# SMARTCONTROL.net
KiCad netlist of a schematic drawn in EAGLE
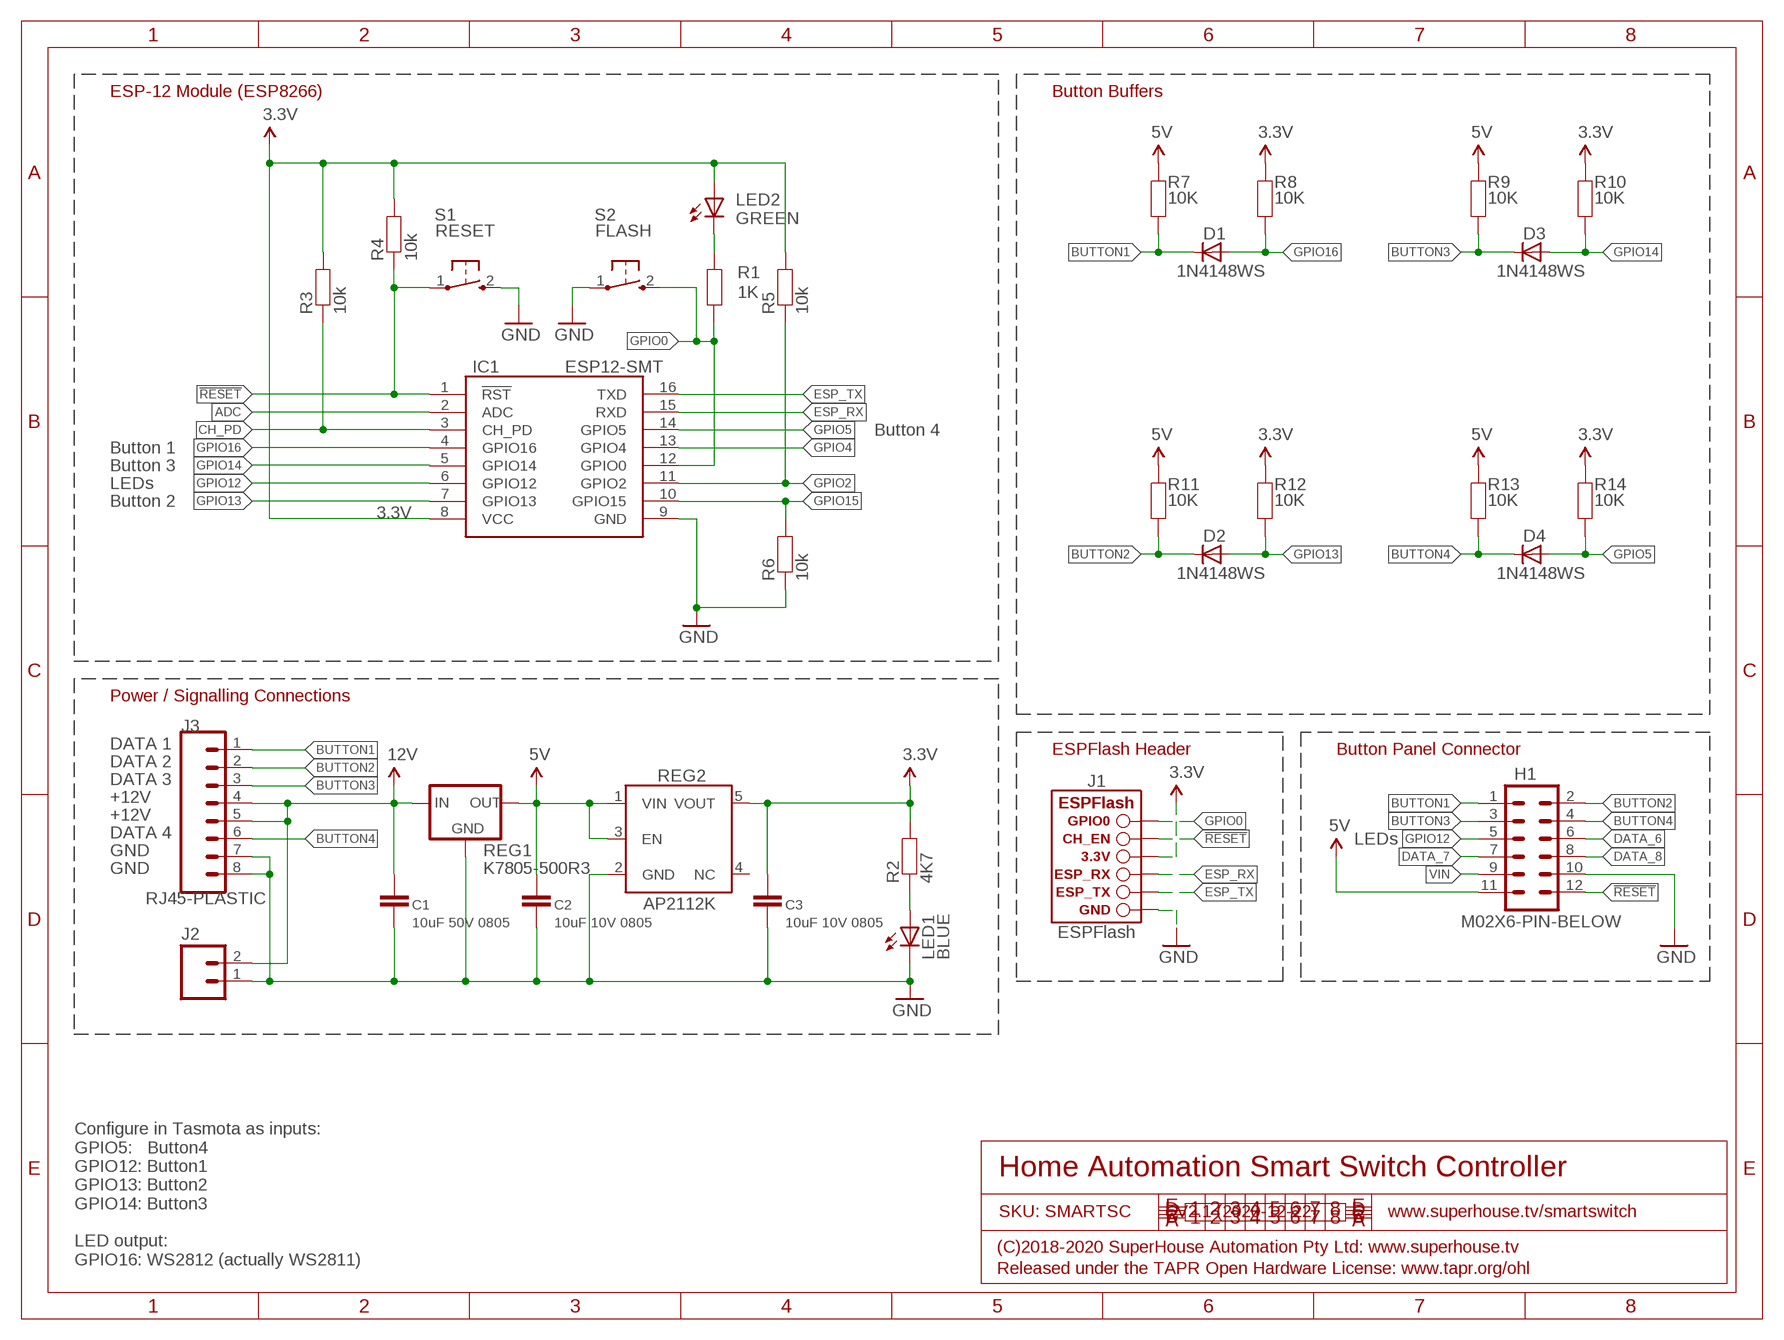
[diagram p0: schematic, sheet 1]

(export (version "E")
  (design (tool "Eeschema 10.0.6"))
  (components
    (comp (ref "C1")
      (value "10uF 50V 0805")
      (footprint "eagle-import:C0805")
      (libsource (lib "eagle-import") (part "CAP0805"))
    )
    (comp (ref "C2")
      (value "10uF 10V 0805")
      (footprint "eagle-import:C0805")
      (libsource (lib "eagle-import") (part "CAP0805"))
    )
    (comp (ref "C3")
      (value "10uF 10V 0805")
      (footprint "eagle-import:C0805")
      (libsource (lib "eagle-import") (part "CAP0805"))
    )
    (comp (ref "D1")
      (value "1N4148WS")
      (footprint "eagle-import:SOD-323")
      (libsource (lib "eagle-import") (part "DIODESOD"))
    )
    (comp (ref "D2")
      (value "1N4148WS")
      (footprint "eagle-import:SOD-323")
      (libsource (lib "eagle-import") (part "DIODESOD"))
    )
    (comp (ref "D3")
      (value "1N4148WS")
      (footprint "eagle-import:SOD-323")
      (libsource (lib "eagle-import") (part "DIODESOD"))
    )
    (comp (ref "D4")
      (value "1N4148WS")
      (footprint "eagle-import:SOD-323")
      (libsource (lib "eagle-import") (part "DIODESOD"))
    )
    (comp (ref "H1")
      (value "M02X6-PIN-BELOW")
      (footprint "eagle-import:2X06-P-BELOW")
      (libsource (lib "eagle-import") (part "M02X6-PIN-BELOW"))
    )
    (comp (ref "IC1")
      (value "ESP12-SMT")
      (footprint "eagle-import:ESP12")
      (libsource (lib "eagle-import") (part "ESP12-SMT"))
    )
    (comp (ref "J1")
      (value "ESPFLASH-1X6-2.54-SOCKET")
      (footprint "eagle-import:1X6-2.54-SOCKET")
      (libsource (lib "eagle-import") (part "ESPFLASH-1X6-2.54-SOCKET"))
    )
    (comp (ref "J2")
      (value "M02-SCREW-5MM")
      (footprint "eagle-import:SCREWTERMINAL-5MM-2")
      (libsource (lib "eagle-import") (part "M02-SCREW-5MM"))
    )
    (comp (ref "J3")
      (value "RJ45-PLASTIC")
      (footprint "eagle-import:RJ45")
      (libsource (lib "eagle-import") (part "RJ45-PLASTIC"))
    )
    (comp (ref "LED1")
      (value "BLUE")
      (footprint "eagle-import:LED-0603")
      (libsource (lib "eagle-import") (part "LED0603"))
    )
    (comp (ref "LED2")
      (value "GREEN")
      (footprint "eagle-import:LED-0603")
      (libsource (lib "eagle-import") (part "LED0603"))
    )
    (comp (ref "R1")
      (value "1K")
      (footprint "eagle-import:R0603")
      (libsource (lib "eagle-import") (part "RESISTOR0603"))
    )
    (comp (ref "R2")
      (value "4K7")
      (footprint "eagle-import:R0603")
      (libsource (lib "eagle-import") (part "RESISTOR0603"))
    )
    (comp (ref "R3")
      (value "10k")
      (footprint "eagle-import:R0603")
      (libsource (lib "eagle-import") (part "RESISTOR0603"))
    )
    (comp (ref "R4")
      (value "10k")
      (footprint "eagle-import:R0603")
      (libsource (lib "eagle-import") (part "RESISTOR0603"))
    )
    (comp (ref "R5")
      (value "10k")
      (footprint "eagle-import:R0603")
      (libsource (lib "eagle-import") (part "RESISTOR0603"))
    )
    (comp (ref "R6")
      (value "10k")
      (footprint "eagle-import:R0603")
      (libsource (lib "eagle-import") (part "RESISTOR0603"))
    )
    (comp (ref "R7")
      (value "10K")
      (footprint "eagle-import:R0603")
      (libsource (lib "eagle-import") (part "RESISTOR0603"))
    )
    (comp (ref "R8")
      (value "10K")
      (footprint "eagle-import:R0603")
      (libsource (lib "eagle-import") (part "RESISTOR0603"))
    )
    (comp (ref "R9")
      (value "10K")
      (footprint "eagle-import:R0603")
      (libsource (lib "eagle-import") (part "RESISTOR0603"))
    )
    (comp (ref "R10")
      (value "10K")
      (footprint "eagle-import:R0603")
      (libsource (lib "eagle-import") (part "RESISTOR0603"))
    )
    (comp (ref "R11")
      (value "10K")
      (footprint "eagle-import:R0603")
      (libsource (lib "eagle-import") (part "RESISTOR0603"))
    )
    (comp (ref "R12")
      (value "10K")
      (footprint "eagle-import:R0603")
      (libsource (lib "eagle-import") (part "RESISTOR0603"))
    )
    (comp (ref "R13")
      (value "10K")
      (footprint "eagle-import:R0603")
      (libsource (lib "eagle-import") (part "RESISTOR0603"))
    )
    (comp (ref "R14")
      (value "10K")
      (footprint "eagle-import:R0603")
      (libsource (lib "eagle-import") (part "RESISTOR0603"))
    )
    (comp (ref "REG1")
      (value "K7805-500R3")
      (footprint "eagle-import:K78XX-500R3")
      (libsource (lib "eagle-import") (part "78XX-K78XX-VERTICAL"))
    )
    (comp (ref "REG2")
      (value "AP2112KSOT25")
      (footprint "eagle-import:SOT23-5")
      (libsource (lib "eagle-import") (part "AP2112KSOT25"))
    )
    (comp (ref "S1")
      (value "RESET")
      (footprint "eagle-import:TACTILE_SMT_3X4X2")
      (libsource (lib "eagle-import") (part "TAC_SWITCH_2PINSMT"))
    )
    (comp (ref "S2")
      (value "FLASH")
      (footprint "eagle-import:TACTILE_SMT_3X4X2")
      (libsource (lib "eagle-import") (part "TAC_SWITCH_2PINSMT"))
    )
  )
  (nets
    (net (code "1") (name "/~{RESET}") (class "Default")
      (node (ref "H1") (pin "12") (pinfunction "12_12") (pintype "passive"))
      (node (ref "IC1") (pin "1") (pinfunction "~{RST}_1") (pintype "bidirectional"))
      (node (ref "J1") (pin "5") (pinfunction "CH_EN_5") (pintype "passive"))
      (node (ref "R4") (pin "1") (pinfunction "1_1") (pintype "passive"))
      (node (ref "S1") (pin "1") (pinfunction "P_1") (pintype "passive"))
    )
    (net (code "2") (name "3.3V") (class "Default")
      (node (ref "C3") (pin "1") (pinfunction "1_1") (pintype "passive"))
      (node (ref "IC1") (pin "8") (pinfunction "VCC_8") (pintype "power_in"))
      (node (ref "J1") (pin "4") (pinfunction "3.3V_4") (pintype "passive"))
      (node (ref "LED2") (pin "A") (pinfunction "A_A") (pintype "passive"))
      (node (ref "R10") (pin "2") (pinfunction "2_2") (pintype "passive"))
      (node (ref "R12") (pin "2") (pinfunction "2_2") (pintype "passive"))
      (node (ref "R14") (pin "2") (pinfunction "2_2") (pintype "passive"))
      (node (ref "R2") (pin "2") (pinfunction "2_2") (pintype "passive"))
      (node (ref "R3") (pin "2") (pinfunction "2_2") (pintype "passive"))
      (node (ref "R4") (pin "2") (pinfunction "2_2") (pintype "passive"))
      (node (ref "R5") (pin "2") (pinfunction "2_2") (pintype "passive"))
      (node (ref "R8") (pin "2") (pinfunction "2_2") (pintype "passive"))
      (node (ref "REG2") (pin "5") (pinfunction "VOUT_5") (pintype "bidirectional"))
    )
    (net (code "3") (name "5V") (class "Default")
      (node (ref "C2") (pin "1") (pinfunction "1_1") (pintype "passive"))
      (node (ref "H1") (pin "11") (pinfunction "11_11") (pintype "passive"))
      (node (ref "R11") (pin "2") (pinfunction "2_2") (pintype "passive"))
      (node (ref "R13") (pin "2") (pinfunction "2_2") (pintype "passive"))
      (node (ref "R7") (pin "2") (pinfunction "2_2") (pintype "passive"))
      (node (ref "R9") (pin "2") (pinfunction "2_2") (pintype "passive"))
      (node (ref "REG1") (pin "3") (pinfunction "OUT_3") (pintype "output"))
      (node (ref "REG2") (pin "1") (pinfunction "VIN_1") (pintype "bidirectional"))
      (node (ref "REG2") (pin "3") (pinfunction "EN_3") (pintype "bidirectional"))
    )
    (net (code "4") (name "12V") (class "Default")
      (node (ref "C1") (pin "1") (pinfunction "1_1") (pintype "passive"))
      (node (ref "J2") (pin "2") (pinfunction "2_2") (pintype "passive"))
      (node (ref "J3") (pin "4") (pinfunction "4_4") (pintype "passive"))
      (node (ref "J3") (pin "5") (pinfunction "5_5") (pintype "passive"))
      (node (ref "REG1") (pin "1") (pinfunction "IN_1") (pintype "input"))
    )
    (net (code "5") (name "ADC") (class "Default")
      (node (ref "IC1") (pin "2") (pinfunction "ADC_2") (pintype "input"))
    )
    (net (code "6") (name "BUTTON1") (class "Default")
      (node (ref "D1") (pin "1") (pinfunction "C_1") (pintype "passive"))
      (node (ref "H1") (pin "1") (pinfunction "1_1") (pintype "passive"))
      (node (ref "J3") (pin "1") (pinfunction "1_1") (pintype "passive"))
      (node (ref "R7") (pin "1") (pinfunction "1_1") (pintype "passive"))
    )
    (net (code "7") (name "BUTTON2") (class "Default")
      (node (ref "D2") (pin "1") (pinfunction "C_1") (pintype "passive"))
      (node (ref "H1") (pin "2") (pinfunction "2_2") (pintype "passive"))
      (node (ref "J3") (pin "2") (pinfunction "2_2") (pintype "passive"))
      (node (ref "R11") (pin "1") (pinfunction "1_1") (pintype "passive"))
    )
    (net (code "8") (name "BUTTON3") (class "Default")
      (node (ref "D3") (pin "1") (pinfunction "C_1") (pintype "passive"))
      (node (ref "H1") (pin "3") (pinfunction "3_3") (pintype "passive"))
      (node (ref "J3") (pin "3") (pinfunction "3_3") (pintype "passive"))
      (node (ref "R9") (pin "1") (pinfunction "1_1") (pintype "passive"))
    )
    (net (code "9") (name "BUTTON4") (class "Default")
      (node (ref "D4") (pin "1") (pinfunction "C_1") (pintype "passive"))
      (node (ref "H1") (pin "4") (pinfunction "4_4") (pintype "passive"))
      (node (ref "J3") (pin "6") (pinfunction "6_6") (pintype "passive"))
      (node (ref "R13") (pin "1") (pinfunction "1_1") (pintype "passive"))
    )
    (net (code "10") (name "CH_PD") (class "Default")
      (node (ref "IC1") (pin "3") (pinfunction "CH_PD_3") (pintype "input"))
      (node (ref "R3") (pin "1") (pinfunction "1_1") (pintype "passive"))
    )
    (net (code "11") (name "DATA_6") (class "Default")
      (node (ref "H1") (pin "6") (pinfunction "6_6") (pintype "passive"))
    )
    (net (code "12") (name "DATA_7") (class "Default")
      (node (ref "H1") (pin "7") (pinfunction "7_7") (pintype "passive"))
    )
    (net (code "13") (name "DATA_8") (class "Default")
      (node (ref "H1") (pin "8") (pinfunction "8_8") (pintype "passive"))
    )
    (net (code "14") (name "ESP_RX") (class "Default")
      (node (ref "IC1") (pin "15") (pinfunction "RXD_15") (pintype "input"))
      (node (ref "J1") (pin "3") (pinfunction "ESP_RX_3") (pintype "passive"))
    )
    (net (code "15") (name "ESP_TX") (class "Default")
      (node (ref "IC1") (pin "16") (pinfunction "TXD_16") (pintype "output"))
      (node (ref "J1") (pin "2") (pinfunction "ESP_TX_2") (pintype "passive"))
    )
    (net (code "16") (name "GND") (class "Default")
      (node (ref "C1") (pin "2") (pinfunction "2_2") (pintype "passive"))
      (node (ref "C2") (pin "2") (pinfunction "2_2") (pintype "passive"))
      (node (ref "C3") (pin "2") (pinfunction "2_2") (pintype "passive"))
      (node (ref "H1") (pin "10") (pinfunction "10_10") (pintype "passive"))
      (node (ref "IC1") (pin "9") (pinfunction "GND_9") (pintype "power_in"))
      (node (ref "J1") (pin "1") (pinfunction "GND_1") (pintype "passive"))
      (node (ref "J2") (pin "1") (pinfunction "1_1") (pintype "passive"))
      (node (ref "J3") (pin "7") (pinfunction "7_7") (pintype "passive"))
      (node (ref "J3") (pin "8") (pinfunction "8_8") (pintype "passive"))
      (node (ref "LED1") (pin "C") (pinfunction "C_C") (pintype "passive"))
      (node (ref "R6") (pin "1") (pinfunction "1_1") (pintype "passive"))
      (node (ref "REG1") (pin "2") (pinfunction "GND_2") (pintype "input"))
      (node (ref "REG2") (pin "2") (pinfunction "GND_2") (pintype "bidirectional"))
      (node (ref "S1") (pin "2") (pinfunction "S_2") (pintype "passive"))
      (node (ref "S2") (pin "1") (pinfunction "P_1") (pintype "passive"))
    )
    (net (code "17") (name "GPIO0") (class "Default")
      (node (ref "IC1") (pin "12") (pinfunction "GPIO0_12") (pintype "bidirectional"))
      (node (ref "J1") (pin "6") (pinfunction "GPIO0_6") (pintype "passive"))
      (node (ref "R1") (pin "2") (pinfunction "2_2") (pintype "passive"))
      (node (ref "S2") (pin "2") (pinfunction "S_2") (pintype "passive"))
    )
    (net (code "18") (name "GPIO2") (class "Default")
      (node (ref "IC1") (pin "11") (pinfunction "GPIO2_11") (pintype "bidirectional"))
      (node (ref "R5") (pin "1") (pinfunction "1_1") (pintype "passive"))
    )
    (net (code "19") (name "GPIO4") (class "Default")
      (node (ref "IC1") (pin "13") (pinfunction "GPIO4_13") (pintype "bidirectional"))
    )
    (net (code "20") (name "GPIO5") (class "Default")
      (node (ref "D4") (pin "2") (pinfunction "A_2") (pintype "passive"))
      (node (ref "IC1") (pin "14") (pinfunction "GPIO5_14") (pintype "bidirectional"))
      (node (ref "R14") (pin "1") (pinfunction "1_1") (pintype "passive"))
    )
    (net (code "21") (name "GPIO12") (class "Default")
      (node (ref "H1") (pin "5") (pinfunction "5_5") (pintype "passive"))
      (node (ref "IC1") (pin "6") (pinfunction "GPIO12_6") (pintype "bidirectional"))
    )
    (net (code "22") (name "GPIO13") (class "Default")
      (node (ref "D2") (pin "2") (pinfunction "A_2") (pintype "passive"))
      (node (ref "IC1") (pin "7") (pinfunction "GPIO13_7") (pintype "bidirectional"))
      (node (ref "R12") (pin "1") (pinfunction "1_1") (pintype "passive"))
    )
    (net (code "23") (name "GPIO14") (class "Default")
      (node (ref "D3") (pin "2") (pinfunction "A_2") (pintype "passive"))
      (node (ref "IC1") (pin "5") (pinfunction "GPIO14_5") (pintype "bidirectional"))
      (node (ref "R10") (pin "1") (pinfunction "1_1") (pintype "passive"))
    )
    (net (code "24") (name "GPIO15") (class "Default")
      (node (ref "IC1") (pin "10") (pinfunction "GPIO15_10") (pintype "bidirectional"))
      (node (ref "R6") (pin "2") (pinfunction "2_2") (pintype "passive"))
    )
    (net (code "25") (name "GPIO16") (class "Default")
      (node (ref "D1") (pin "2") (pinfunction "A_2") (pintype "passive"))
      (node (ref "IC1") (pin "4") (pinfunction "GPIO16_4") (pintype "bidirectional"))
      (node (ref "R8") (pin "1") (pinfunction "1_1") (pintype "passive"))
    )
    (net (code "26") (name "Net-(LED1-PadA)") (class "Default")
      (node (ref "LED1") (pin "A") (pinfunction "A_A") (pintype "passive"))
      (node (ref "R2") (pin "1") (pinfunction "1_1") (pintype "passive"))
    )
    (net (code "27") (name "Net-(LED2-PadC)") (class "Default")
      (node (ref "LED2") (pin "C") (pinfunction "C_C") (pintype "passive"))
      (node (ref "R1") (pin "1") (pinfunction "1_1") (pintype "passive"))
    )
    (net (code "28") (name "VIN") (class "Default")
      (node (ref "H1") (pin "9") (pinfunction "9_9") (pintype "passive"))
    )
    (net (code "29") (name "unconnected-(REG2-NC-Pad4)") (class "Default")
      (node (ref "REG2") (pin "4") (pinfunction "NC_4") (pintype "bidirectional"))
    )
  )
)
